# SAM70.net
KiCad netlist of a schematic drawn in Altium Designer
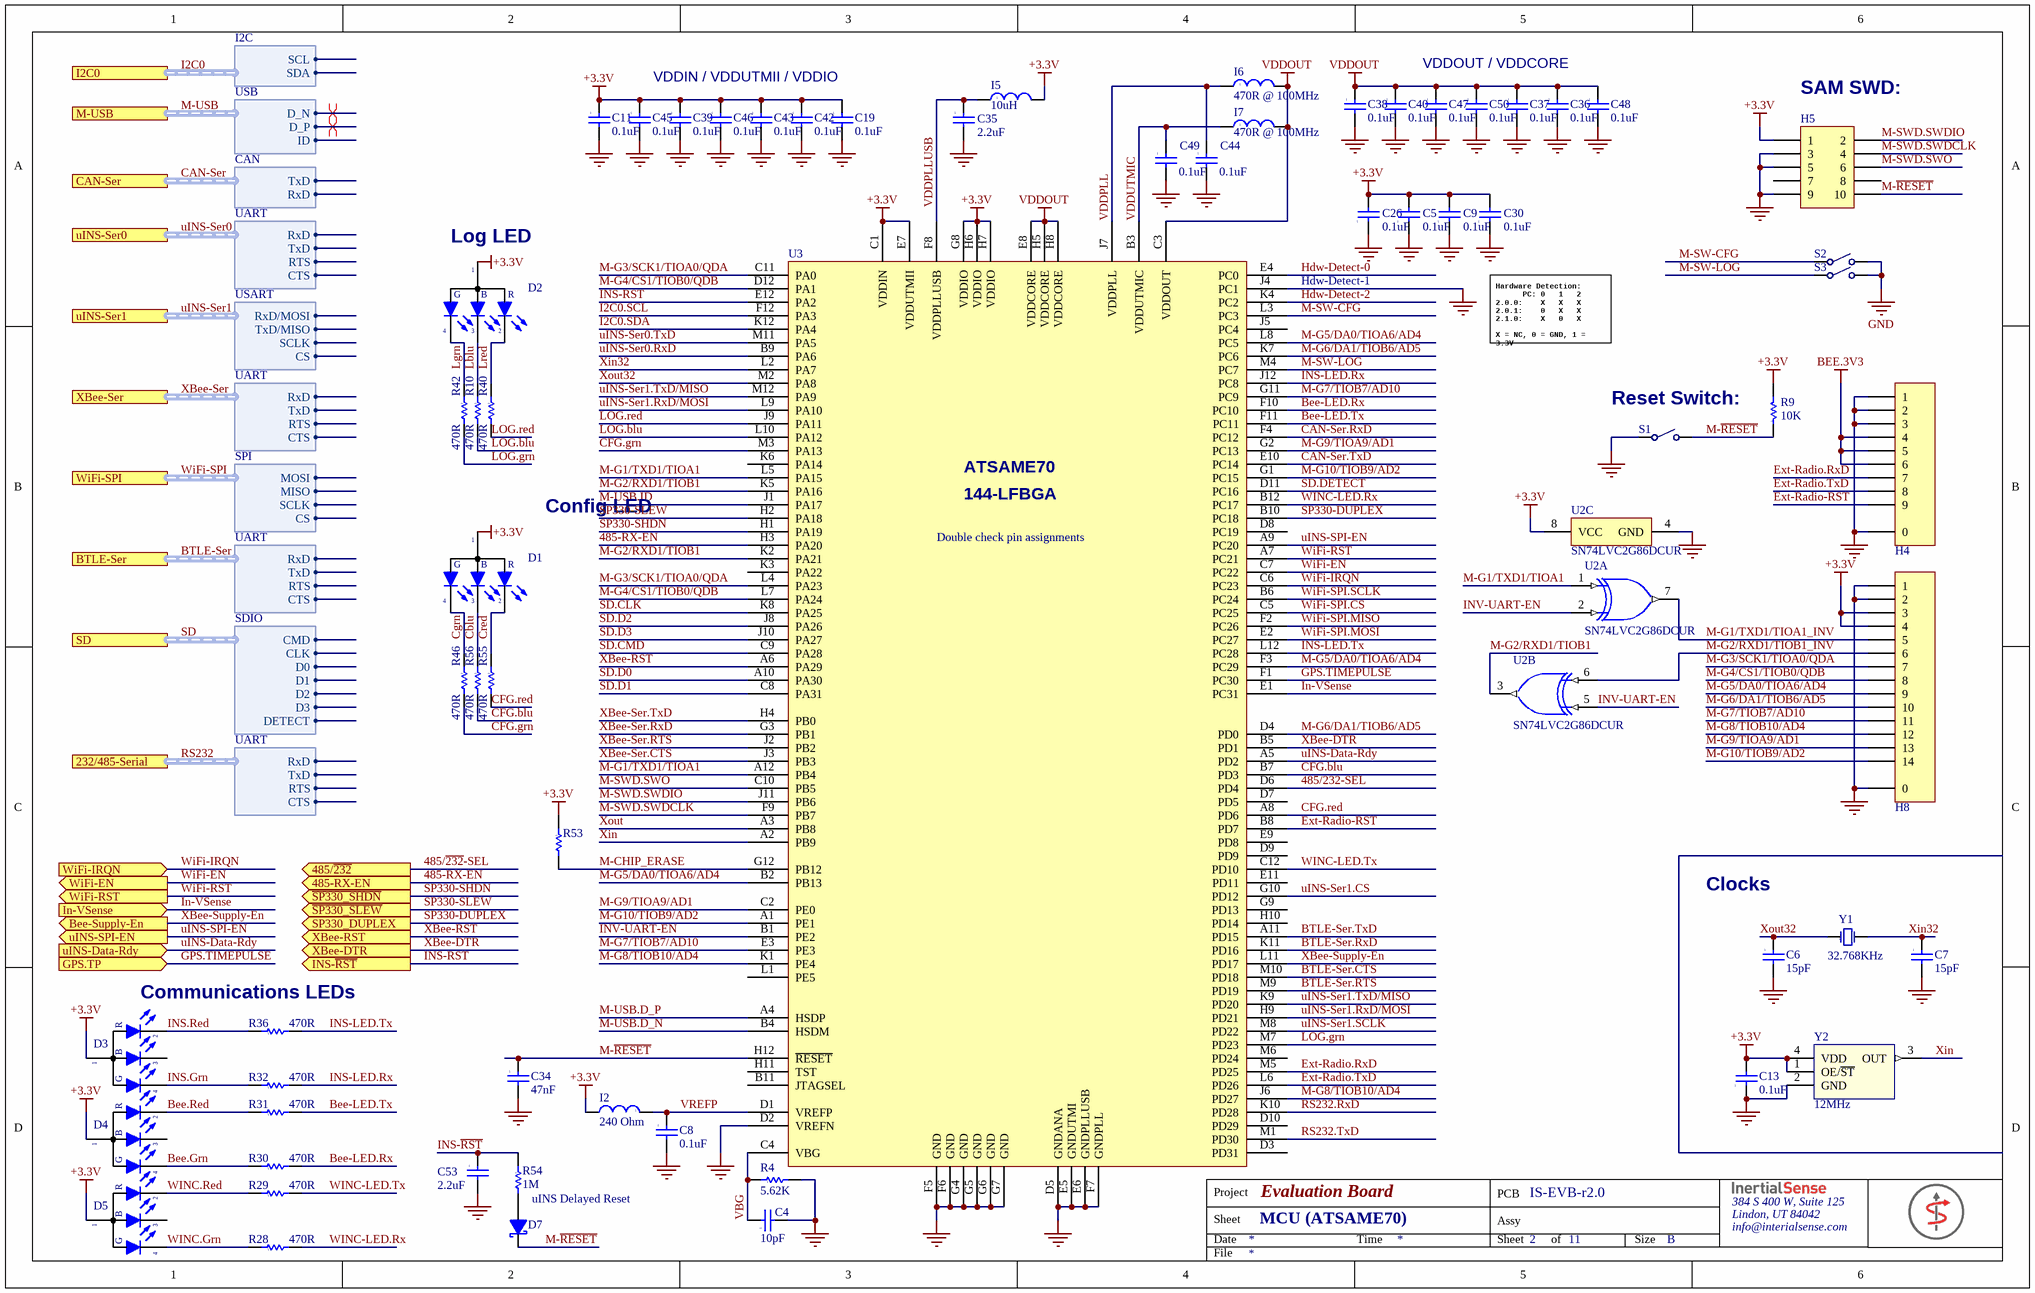
[diagram p0: SAM70.SchDoc]

(export (version "E")
  (design (tool "Eeschema 10.0.6"))
  (components
    (comp (ref "C4")
      (value "10pF")
      (footprint "0402")
      (description "CAP CER 10PF 50V C0G 0402")
      (fields
        (field (name "MANUFACTURER") "TDK")
        (field (name "MANUFACTURER PART NUMBER") "C1005C0G1H100D050BA")
        (field (name "PUBLISHER") "Altium Limited")
      )
      (libsource (lib "General") (part "Cap"))
    )
    (comp (ref "C5")
      (value "0.1uF")
      (footprint "0402")
      (description "CAP CER .10UF 50V X7R 10% 0402")
      (fields
        (field (name "MANUFACTURER") "TDK Corporation")
        (field (name "MANUFACTURER PART NUMBER") "C1005X7R1H104K")
        (field (name "PUBLISHER") "Altium Limited")
      )
      (libsource (lib "") (part "Cap_1"))
    )
    (comp (ref "C6")
      (value "15pF")
      (footprint "0402")
      (description "CAP CER 15PF 16V C0G/NP0 0402")
      (fields
        (field (name "MANUFACTURER") "KEMET")
        (field (name "MANUFACTURER PART NUMBER") "C0402C150J4GACTU")
        (field (name "PUBLISHER") "Altium Limited")
      )
      (libsource (lib "General") (part "Cap"))
    )
    (comp (ref "C7")
      (value "15pF")
      (footprint "0402")
      (description "CAP CER 15PF 16V C0G/NP0 0402")
      (fields
        (field (name "MANUFACTURER") "KEMET")
        (field (name "MANUFACTURER PART NUMBER") "C0402C150J4GACTU")
        (field (name "PUBLISHER") "Altium Limited")
      )
      (libsource (lib "General") (part "Cap"))
    )
    (comp (ref "C8")
      (value "0.1uF")
      (footprint "0201")
      (description "CAP CER 0.1UF 25V X5R 0201")
      (fields
        (field (name "MANUFACTURER") "Murata")
        (field (name "MANUFACTURER PART NUMBER") "GRM033R6YA104KE14D")
        (field (name "PUBLISHER") "Altium Limited")
      )
      (libsource (lib "General") (part "Cap"))
    )
    (comp (ref "C9")
      (value "0.1uF")
      (footprint "0402")
      (description "CAP CER .10UF 50V X7R 10% 0402")
      (fields
        (field (name "MANUFACTURER") "TDK Corporation")
        (field (name "MANUFACTURER PART NUMBER") "C1005X7R1H104K")
        (field (name "PUBLISHER") "Altium Limited")
      )
      (libsource (lib "") (part "Cap_1"))
    )
    (comp (ref "C11")
      (value "0.1uF")
      (footprint "0201")
      (description "CAP CER 0.1UF 25V X5R 0201")
      (fields
        (field (name "MANUFACTURER") "Murata")
        (field (name "MANUFACTURER PART NUMBER") "GRM033R6YA104KE14D")
        (field (name "PUBLISHER") "Altium Limited")
      )
      (libsource (lib "General") (part "Cap"))
    )
    (comp (ref "C13")
      (value "0.1uF")
      (footprint "0402")
      (description "CAP CER .10UF 50V X7R 10% 0402")
      (fields
        (field (name "MANUFACTURER") "TDK Corporation")
        (field (name "MANUFACTURER PART NUMBER") "C1005X7R1H104K")
        (field (name "PUBLISHER") "Altium Limited")
      )
      (libsource (lib "") (part "Cap_1"))
    )
    (comp (ref "C19")
      (value "0.1uF")
      (footprint "0201")
      (description "CAP CER 0.1UF 25V X5R 0201")
      (fields
        (field (name "MANUFACTURER") "Murata")
        (field (name "MANUFACTURER PART NUMBER") "GRM033R6YA104KE14D")
        (field (name "PUBLISHER") "Altium Limited")
      )
      (libsource (lib "General") (part "Cap"))
    )
    (comp (ref "C26")
      (value "0.1uF")
      (footprint "0402")
      (description "CAP CER .10UF 50V X7R 10% 0402")
      (fields
        (field (name "MANUFACTURER") "TDK Corporation")
        (field (name "MANUFACTURER PART NUMBER") "C1005X7R1H104K")
        (field (name "PUBLISHER") "Altium Limited")
      )
      (libsource (lib "") (part "Cap_1"))
    )
    (comp (ref "C30")
      (value "0.1uF")
      (footprint "0402")
      (description "CAP CER .10UF 50V X7R 10% 0402")
      (fields
        (field (name "MANUFACTURER") "TDK Corporation")
        (field (name "MANUFACTURER PART NUMBER") "C1005X7R1H104K")
        (field (name "PUBLISHER") "Altium Limited")
      )
      (libsource (lib "") (part "Cap_1"))
    )
    (comp (ref "C34")
      (value "47nF")
      (footprint "0402")
      (description "CAP CER 0.047UF 16V Y5V 0402")
      (fields
        (field (name "MANUFACTURER") "Yageo")
        (field (name "MANUFACTURER PART NUMBER") "CC0402ZRY5V7BB473")
        (field (name "PUBLISHER") "Altium Limited")
      )
      (libsource (lib "General") (part "Cap"))
    )
    (comp (ref "C35")
      (value "Cap")
      (footprint "0603")
      (description "CAP CER 2.2UF 6.3V X5R 0603")
      (fields
        (field (name "MANUFACTURER") "Samsung")
        (field (name "MANUFACTURER PART NUMBER") "CL10A225KQ8NNWC")
        (field (name "CAPACITANCE") "2.2uF")
      )
      (libsource (lib "General") (part "Cap"))
    )
    (comp (ref "C36")
      (value "0.1uF")
      (footprint "0201")
      (description "CAP CER 0.1UF 25V X5R 0201")
      (fields
        (field (name "MANUFACTURER") "Murata")
        (field (name "MANUFACTURER PART NUMBER") "GRM033R6YA104KE14D")
        (field (name "PUBLISHER") "Altium Limited")
      )
      (libsource (lib "General") (part "Cap"))
    )
    (comp (ref "C37")
      (value "0.1uF")
      (footprint "0201")
      (description "CAP CER 0.1UF 25V X5R 0201")
      (fields
        (field (name "MANUFACTURER") "Murata")
        (field (name "MANUFACTURER PART NUMBER") "GRM033R6YA104KE14D")
        (field (name "PUBLISHER") "Altium Limited")
      )
      (libsource (lib "General") (part "Cap"))
    )
    (comp (ref "C38")
      (value "0.1uF")
      (footprint "0201")
      (description "CAP CER 0.1UF 25V X5R 0201")
      (fields
        (field (name "MANUFACTURER") "Murata")
        (field (name "MANUFACTURER PART NUMBER") "GRM033R6YA104KE14D")
        (field (name "PUBLISHER") "Altium Limited")
      )
      (libsource (lib "General") (part "Cap"))
    )
    (comp (ref "C39")
      (value "0.1uF")
      (footprint "0201")
      (description "CAP CER 0.1UF 25V X5R 0201")
      (fields
        (field (name "MANUFACTURER") "Murata")
        (field (name "MANUFACTURER PART NUMBER") "GRM033R6YA104KE14D")
        (field (name "PUBLISHER") "Altium Limited")
      )
      (libsource (lib "General") (part "Cap"))
    )
    (comp (ref "C40")
      (value "0.1uF")
      (footprint "0201")
      (description "CAP CER 0.1UF 25V X5R 0201")
      (fields
        (field (name "MANUFACTURER") "Murata")
        (field (name "MANUFACTURER PART NUMBER") "GRM033R6YA104KE14D")
        (field (name "PUBLISHER") "Altium Limited")
      )
      (libsource (lib "General") (part "Cap"))
    )
    (comp (ref "C42")
      (value "0.1uF")
      (footprint "0201")
      (description "CAP CER 0.1UF 25V X5R 0201")
      (fields
        (field (name "MANUFACTURER") "Murata")
        (field (name "MANUFACTURER PART NUMBER") "GRM033R6YA104KE14D")
        (field (name "PUBLISHER") "Altium Limited")
      )
      (libsource (lib "General") (part "Cap"))
    )
    (comp (ref "C43")
      (value "0.1uF")
      (footprint "0201")
      (description "CAP CER 0.1UF 25V X5R 0201")
      (fields
        (field (name "MANUFACTURER") "Murata")
        (field (name "MANUFACTURER PART NUMBER") "GRM033R6YA104KE14D")
        (field (name "PUBLISHER") "Altium Limited")
      )
      (libsource (lib "General") (part "Cap"))
    )
    (comp (ref "C44")
      (value "0.1uF")
      (footprint "0201")
      (description "CAP CER 0.1UF 25V X5R 0201")
      (fields
        (field (name "MANUFACTURER") "Murata")
        (field (name "MANUFACTURER PART NUMBER") "GRM033R6YA104KE14D")
        (field (name "PUBLISHER") "Altium Limited")
      )
      (libsource (lib "General") (part "Cap"))
    )
    (comp (ref "C45")
      (value "0.1uF")
      (footprint "0201")
      (description "CAP CER 0.1UF 25V X5R 0201")
      (fields
        (field (name "MANUFACTURER") "Murata")
        (field (name "MANUFACTURER PART NUMBER") "GRM033R6YA104KE14D")
        (field (name "PUBLISHER") "Altium Limited")
      )
      (libsource (lib "General") (part "Cap"))
    )
    (comp (ref "C46")
      (value "0.1uF")
      (footprint "0201")
      (description "CAP CER 0.1UF 25V X5R 0201")
      (fields
        (field (name "MANUFACTURER") "Murata")
        (field (name "MANUFACTURER PART NUMBER") "GRM033R6YA104KE14D")
        (field (name "PUBLISHER") "Altium Limited")
      )
      (libsource (lib "General") (part "Cap"))
    )
    (comp (ref "C47")
      (value "0.1uF")
      (footprint "0201")
      (description "CAP CER 0.1UF 25V X5R 0201")
      (fields
        (field (name "MANUFACTURER") "Murata")
        (field (name "MANUFACTURER PART NUMBER") "GRM033R6YA104KE14D")
        (field (name "PUBLISHER") "Altium Limited")
      )
      (libsource (lib "General") (part "Cap"))
    )
    (comp (ref "C48")
      (value "0.1uF")
      (footprint "0201")
      (description "CAP CER 0.1UF 25V X5R 0201")
      (fields
        (field (name "MANUFACTURER") "Murata")
        (field (name "MANUFACTURER PART NUMBER") "GRM033R6YA104KE14D")
        (field (name "PUBLISHER") "Altium Limited")
      )
      (libsource (lib "General") (part "Cap"))
    )
    (comp (ref "C49")
      (value "0.1uF")
      (footprint "0201")
      (description "CAP CER 0.1UF 25V X5R 0201")
      (fields
        (field (name "MANUFACTURER") "Murata")
        (field (name "MANUFACTURER PART NUMBER") "GRM033R6YA104KE14D")
        (field (name "PUBLISHER") "Altium Limited")
      )
      (libsource (lib "General") (part "Cap"))
    )
    (comp (ref "C50")
      (value "0.1uF")
      (footprint "0201")
      (description "CAP CER 0.1UF 25V X5R 0201")
      (fields
        (field (name "MANUFACTURER") "Murata")
        (field (name "MANUFACTURER PART NUMBER") "GRM033R6YA104KE14D")
        (field (name "PUBLISHER") "Altium Limited")
      )
      (libsource (lib "General") (part "Cap"))
    )
    (comp (ref "C53")
      (value "Cap")
      (footprint "0603")
      (description "CAP CER 2.2UF 6.3V X5R 0603")
      (fields
        (field (name "MANUFACTURER") "Samsung")
        (field (name "MANUFACTURER PART NUMBER") "CL10A225KQ8NNWC")
        (field (name "CAPACITANCE") "2.2uF")
      )
      (libsource (lib "General") (part "Cap"))
    )
    (comp (ref "D1")
      (value "LED-RGB")
      (footprint "LED0404")
      (description "LED RGB DIFFUSED 0404 SMD")
      (fields
        (field (name "MANUFACTURER") "Rohm Semiconductor")
        (field (name "MANUFACTURER PART NUMBER") "SMLP34RGB2W3")
        (field (name "PUBLISHER") "Altium Limited")
      )
      (libsource (lib "General") (part "LED-RGB"))
    )
    (comp (ref "D2")
      (value "LED-RGB")
      (footprint "LED0404")
      (description "LED RGB DIFFUSED 0404 SMD")
      (fields
        (field (name "MANUFACTURER") "Rohm Semiconductor")
        (field (name "MANUFACTURER PART NUMBER") "SMLP34RGB2W3")
        (field (name "PUBLISHER") "Altium Limited")
      )
      (libsource (lib "General") (part "LED-RGB"))
    )
    (comp (ref "D3")
      (value "LED-RGB")
      (footprint "LED0404")
      (description "LED RGB DIFFUSED 0404 SMD")
      (fields
        (field (name "MANUFACTURER") "Rohm Semiconductor")
        (field (name "MANUFACTURER PART NUMBER") "SMLP34RGB2W3")
        (field (name "PUBLISHER") "Altium Limited")
      )
      (libsource (lib "General") (part "LED-RGB"))
    )
    (comp (ref "D4")
      (value "LED-RGB")
      (footprint "LED0404")
      (description "LED RGB DIFFUSED 0404 SMD")
      (fields
        (field (name "MANUFACTURER") "Rohm Semiconductor")
        (field (name "MANUFACTURER PART NUMBER") "SMLP34RGB2W3")
        (field (name "PUBLISHER") "Altium Limited")
      )
      (libsource (lib "General") (part "LED-RGB"))
    )
    (comp (ref "D5")
      (value "LED-RGB")
      (footprint "LED0404")
      (description "LED RGB DIFFUSED 0404 SMD")
      (fields
        (field (name "MANUFACTURER") "Rohm Semiconductor")
        (field (name "MANUFACTURER PART NUMBER") "SMLP34RGB2W3")
        (field (name "PUBLISHER") "Altium Limited")
      )
      (libsource (lib "General") (part "LED-RGB"))
    )
    (comp (ref "D7")
      (value "Diode - Schottky")
      (footprint "D0603B")
      (description "DIODE SCHOTTKY 30V 2A 0603")
      (fields
        (field (name "MANUFACTURER") "Vishay")
        (field (name "MANUFACTURER PART NUMBER") "VSKY20301608-G4-08")
      )
      (libsource (lib "General") (part "Diode - Schottky"))
    )
    (comp (ref "H4")
      (value "Hdr - 9pin - mount")
      (footprint "SM09B-GHS-TB(LF)(SN)")
      (description "CONN HEADER GH SIDE 9POS 1.25MM")
      (fields
        (field (name "MANUFACTURER") "JST")
        (field (name "MANUFACTURER PART NUMBER") "SM09B-GHS-TB(LF)(SN)")
      )
      (libsource (lib "Connectors") (part "Hdr - 9pin - mount"))
    )
    (comp (ref "H5")
      (value "Hdr - 5x2pin")
      (footprint "FTSH-105-01-L-DV-K-A-P")
      (description "CONN HEADER 10POS DUAL .05\" SMD")
      (fields
        (field (name "MANUFACTURER") "Samtec")
        (field (name "MANUFACTURER PART NUMBER") "FTSH-105-01-L-DV-K-A-P")
      )
      (libsource (lib "Connectors") (part "Hdr - 5x2pin"))
    )
    (comp (ref "H8")
      (value "Hdr - 14pin - mount")
      (footprint "SM14B-GHS-TB(LF)(SN)")
      (description "CONN HEADER GH SIDE 14POS 1.25MM")
      (fields
        (field (name "MANUFACTURER") "JST")
        (field (name "MANUFACTURER PART NUMBER") "SM14B-GHS-TB(LF)(SN)")
      )
      (libsource (lib "Connectors") (part "Hdr - 14pin - mount"))
    )
    (comp (ref "I2")
      (value "240 Ohm")
      (footprint "0201")
      (description "FERRITE BEAD 240 OHM 0201 1LN")
      (fields
        (field (name "MANUFACTURER") "TDK Corporation")
        (field (name "MANUFACTURER PART NUMBER") "MMZ0603S241HT000")
      )
      (libsource (lib "General") (part "Inductor"))
    )
    (comp (ref "I5")
      (value "Inductor")
      (footprint "0806")
      (description "FIXED IND 10UH 350MA 1.066 OHM")
      (fields
        (field (name "MANUFACTURER") "Taiyo Yuden")
        (field (name "MANUFACTURER PART NUMBER") "CBC2016T100M")
        (field (name "INDUCTANCE") "10uH")
      )
      (libsource (lib "") (part "Inductor_1"))
    )
    (comp (ref "I6")
      (value "470R @ 100MHz")
      (footprint "0402")
      (description "FERRITE BEAD 470 OHM 0402")
      (fields
        (field (name "MANUFACTURER") "Taiyo Yuden")
        (field (name "MANUFACTURER PART NUMBER") "BK1005HM471-T")
      )
      (libsource (lib "") (part "Inductor_1"))
    )
    (comp (ref "I7")
      (value "470R @ 100MHz")
      (footprint "0402")
      (description "FERRITE BEAD 470 OHM 0402")
      (fields
        (field (name "MANUFACTURER") "Taiyo Yuden")
        (field (name "MANUFACTURER PART NUMBER") "BK1005HM471-T")
      )
      (libsource (lib "") (part "Inductor_1"))
    )
    (comp (ref "R4")
      (value "5.62K")
      (footprint "R0402")
      (description "RES SMD 5.62K OHM 1% 1/10W 0402")
      (fields
        (field (name "MANUFACTURER") "Panasonic")
        (field (name "MANUFACTURER PART NUMBER") "ERJ-2RKF5621X")
      )
      (libsource (lib "General") (part "Res"))
    )
    (comp (ref "R9")
      (value "10K")
      (footprint "R0402")
      (description "RES 10K OHM 1/16W 1% 0402 SMD")
      (fields
        (field (name "MANUFACTURER") "Panasonic")
        (field (name "MANUFACTURER PART NUMBER") "ERJ-2RKF1002X")
      )
      (libsource (lib "") (part "Res_1"))
    )
    (comp (ref "R10")
      (value "470R")
      (footprint "R0402")
      (description "RES SMD 470 OHM 5% 1/16W 0402")
      (fields
        (field (name "MANUFACTURER") "Vishay Dale")
        (field (name "MANUFACTURER PART NUMBER") "CRCW0402470RJNED")
      )
      (libsource (lib "General") (part "Res"))
    )
    (comp (ref "R28")
      (value "470R")
      (footprint "R0402")
      (description "RES SMD 470 OHM 5% 1/16W 0402")
      (fields
        (field (name "MANUFACTURER") "Vishay Dale")
        (field (name "MANUFACTURER PART NUMBER") "CRCW0402470RJNED")
      )
      (libsource (lib "General") (part "Res"))
    )
    (comp (ref "R29")
      (value "470R")
      (footprint "R0402")
      (description "RES SMD 470 OHM 5% 1/16W 0402")
      (fields
        (field (name "MANUFACTURER") "Vishay Dale")
        (field (name "MANUFACTURER PART NUMBER") "CRCW0402470RJNED")
      )
      (libsource (lib "General") (part "Res"))
    )
    (comp (ref "R30")
      (value "470R")
      (footprint "R0402")
      (description "RES SMD 470 OHM 5% 1/16W 0402")
      (fields
        (field (name "MANUFACTURER") "Vishay Dale")
        (field (name "MANUFACTURER PART NUMBER") "CRCW0402470RJNED")
      )
      (libsource (lib "General") (part "Res"))
    )
    (comp (ref "R31")
      (value "470R")
      (footprint "R0402")
      (description "RES SMD 470 OHM 5% 1/16W 0402")
      (fields
        (field (name "MANUFACTURER") "Vishay Dale")
        (field (name "MANUFACTURER PART NUMBER") "CRCW0402470RJNED")
      )
      (libsource (lib "General") (part "Res"))
    )
    (comp (ref "R32")
      (value "470R")
      (footprint "R0402")
      (description "RES SMD 470 OHM 5% 1/16W 0402")
      (fields
        (field (name "MANUFACTURER") "Vishay Dale")
        (field (name "MANUFACTURER PART NUMBER") "CRCW0402470RJNED")
      )
      (libsource (lib "General") (part "Res"))
    )
    (comp (ref "R36")
      (value "470R")
      (footprint "R0402")
      (description "RES SMD 470 OHM 5% 1/16W 0402")
      (fields
        (field (name "MANUFACTURER") "Vishay Dale")
        (field (name "MANUFACTURER PART NUMBER") "CRCW0402470RJNED")
      )
      (libsource (lib "General") (part "Res"))
    )
    (comp (ref "R40")
      (value "470R")
      (footprint "R0402")
      (description "RES SMD 470 OHM 5% 1/16W 0402")
      (fields
        (field (name "MANUFACTURER") "Vishay Dale")
        (field (name "MANUFACTURER PART NUMBER") "CRCW0402470RJNED")
      )
      (libsource (lib "General") (part "Res"))
    )
    (comp (ref "R42")
      (value "470R")
      (footprint "R0402")
      (description "RES SMD 470 OHM 5% 1/16W 0402")
      (fields
        (field (name "MANUFACTURER") "Vishay Dale")
        (field (name "MANUFACTURER PART NUMBER") "CRCW0402470RJNED")
      )
      (libsource (lib "General") (part "Res"))
    )
    (comp (ref "R46")
      (value "470R")
      (footprint "R0402")
      (description "RES SMD 470 OHM 5% 1/16W 0402")
      (fields
        (field (name "MANUFACTURER") "Vishay Dale")
        (field (name "MANUFACTURER PART NUMBER") "CRCW0402470RJNED")
      )
      (libsource (lib "General") (part "Res"))
    )
    (comp (ref "R53")
      (value "Res")
      (footprint "R0402")
      (description "RES SMD 0402 NO LOAD")
      (libsource (lib "General") (part "Res"))
    )
    (comp (ref "R54")
      (value "1M")
      (footprint "R0402")
      (description "RES SMD 1M OHM 1% 1/16W 0402")
      (fields (field (name "TOLERANCE") "1%") (field (name "Comment") "Res"))
      (libsource (lib "General") (part "Res"))
    )
    (comp (ref "R55")
      (value "470R")
      (footprint "R0402")
      (description "RES SMD 470 OHM 5% 1/16W 0402")
      (fields
        (field (name "MANUFACTURER") "Vishay Dale")
        (field (name "MANUFACTURER PART NUMBER") "CRCW0402470RJNED")
      )
      (libsource (lib "General") (part "Res"))
    )
    (comp (ref "R56")
      (value "470R")
      (footprint "R0402")
      (description "RES SMD 470 OHM 5% 1/16W 0402")
      (fields
        (field (name "MANUFACTURER") "Vishay Dale")
        (field (name "MANUFACTURER PART NUMBER") "CRCW0402470RJNED")
      )
      (libsource (lib "General") (part "Res"))
    )
    (comp (ref "S1")
      (value "SPST Switch")
      (footprint "PTS810")
      (description "SWITCH TACTILE SPST-NO 0.05A 16V")
      (fields
        (field (name "MANUFACTURER") "ITT C&K")
        (field (name "MANUFACTURER PART NUMBER") "PTS810SJK250SMTRLFS")
      )
      (libsource (lib "General") (part "Switch SPST"))
    )
    (comp (ref "S2")
      (value "SPST Switch")
      (footprint "PTS810")
      (description "SWITCH TACTILE SPST-NO 0.05A 16V")
      (fields
        (field (name "MANUFACTURER") "ITT C&K")
        (field (name "MANUFACTURER PART NUMBER") "PTS810SJK250SMTRLFS")
      )
      (libsource (lib "General") (part "Switch SPST"))
    )
    (comp (ref "S3")
      (value "SPST Switch")
      (footprint "PTS810")
      (description "SWITCH TACTILE SPST-NO 0.05A 16V")
      (fields
        (field (name "MANUFACTURER") "ITT C&K")
        (field (name "MANUFACTURER PART NUMBER") "PTS810SJK250SMTRLFS")
      )
      (libsource (lib "General") (part "Switch SPST"))
    )
    (comp (ref "U2")
      (value "SN74LVC2G86DCUR")
      (footprint "DCU0008A_N")
      (description "IC GATE XOR 2CH 2-INP US8")
      (fields
        (field (name "GENERIC PART NUMBER") "SN74LVC2G86")
        (field (name "MANUFACTURER") "Texas Instruments")
      )
      (libsource (lib "TI_Logic_Little_Logic") (part "SN74LVC2G86DCUR"))
    )
    (comp (ref "U3")
      (value "ATSAME70-144")
      (footprint "BGA144C80P12X12_1000X1000X140")
      (description "IC MCU 32BIT 1MB FLASH 144LFBGA")
      (fields
        (field (name "MANUFACTURER") "Microchip")
        (field (name "MANUFACTURER PART NUMBER") "ATSAME70Q20B-CNT")
      )
      (libsource (lib "ICs") (part "ATSAME70-144"))
    )
    (comp (ref "Y1")
      (value "32.768KHz")
      (footprint "CRYMP2012X06L")
      (description "CRYSTAL 32.7680KHZ 9PF SMD")
      (fields
        (field (name "MANUFACTURER") "Abracon LLC")
        (field (name "MANUFACTURER PART NUMBER") "ABS06-32.768KHZ-9-1-T")
      )
      (libsource (lib "General") (part "Crystal"))
    )
    (comp (ref "Y2")
      (value "12MHz")
      (footprint "ABM10_2.5_x_2.0")
      (description "OSC XO 12.000MHZ HCMOS SMD")
      (fields
        (field (name "MANUFACTURER") "ECS Inc.")
        (field (name "MANUFACTURER PART NUMBER") "ECS-2520S33-120-FN-TR")
      )
      (libsource (lib "General") (part "Oscillator2"))
    )
  )
  (nets
    (net (code "11") (name "+3.3V") (class "Default")
      (node (ref "C11") (pin "1") (pinfunction "1_1") (pintype "passive"))
      (node (ref "C13") (pin "2") (pinfunction "2_2") (pintype "passive"))
      (node (ref "C19") (pin "1") (pinfunction "1_1") (pintype "passive"))
      (node (ref "C26") (pin "2") (pinfunction "2_2") (pintype "passive"))
      (node (ref "C30") (pin "2") (pinfunction "2_2") (pintype "passive"))
      (node (ref "C39") (pin "1") (pinfunction "1_1") (pintype "passive"))
      (node (ref "C42") (pin "1") (pinfunction "1_1") (pintype "passive"))
      (node (ref "C43") (pin "1") (pinfunction "1_1") (pintype "passive"))
      (node (ref "C45") (pin "1") (pinfunction "1_1") (pintype "passive"))
      (node (ref "C46") (pin "1") (pinfunction "1_1") (pintype "passive"))
      (node (ref "C5") (pin "2") (pinfunction "2_2") (pintype "passive"))
      (node (ref "C9") (pin "2") (pinfunction "2_2") (pintype "passive"))
      (node (ref "D1") (pin "1") (pinfunction "1_1") (pintype "passive"))
      (node (ref "D2") (pin "1") (pinfunction "1_1") (pintype "passive"))
      (node (ref "D3") (pin "1") (pinfunction "1_1") (pintype "passive"))
      (node (ref "D4") (pin "1") (pinfunction "1_1") (pintype "passive"))
      (node (ref "D5") (pin "1") (pinfunction "1_1") (pintype "passive"))
      (node (ref "H5") (pin "1") (pinfunction "1_1") (pintype "passive"))
      (node (ref "H8") (pin "3") (pinfunction "3_3") (pintype "passive"))
      (node (ref "H8") (pin "4") (pinfunction "4_4") (pintype "passive"))
      (node (ref "I2") (pin "2") (pinfunction "2_2") (pintype "passive"))
      (node (ref "I5") (pin "2") (pinfunction "2_2") (pintype "passive"))
      (node (ref "R53") (pin "1") (pinfunction "1_1") (pintype "passive"))
      (node (ref "R9") (pin "2") (pinfunction "2_2") (pintype "passive"))
      (node (ref "U2") (pin "8") (pinfunction "VCC_8") (pintype "power_in"))
      (node (ref "U3") (pin "C1") (pinfunction "VDDIN_C1") (pintype "passive"))
      (node (ref "U3") (pin "E7") (pinfunction "VDDUTMII_E7") (pintype "passive"))
      (node (ref "U3") (pin "G8") (pinfunction "VDDIO_G8") (pintype "passive"))
      (node (ref "U3") (pin "H6") (pinfunction "VDDIO_H6") (pintype "passive"))
      (node (ref "U3") (pin "H7") (pinfunction "VDDIO_H7") (pintype "passive"))
      (node (ref "Y2") (pin "1") (pinfunction "OE/~{ST}_1") (pintype "passive"))
      (node (ref "Y2") (pin "4") (pinfunction "VDD_4") (pintype "passive"))
    )
    (net (code "12") (name "/485-RX-EN") (class "Default")
      (node (ref "U3") (pin "H3") (pinfunction "PA20_H3") (pintype "passive"))
    )
    (net (code "13") (name "/485{slash}~{232}-SEL") (class "Default")
      (node (ref "U3") (pin "D6") (pinfunction "PD4_D6") (pintype "passive"))
    )
    (net (code "14") (name "/BTLE-Ser.CTS") (class "Default")
      (node (ref "U3") (pin "M10") (pinfunction "PD18_M10") (pintype "passive"))
    )
    (net (code "15") (name "/BTLE-Ser.RTS") (class "Default")
      (node (ref "U3") (pin "M9") (pinfunction "PD19_M9") (pintype "passive"))
    )
    (net (code "16") (name "/BTLE-Ser.RxD") (class "Default")
      (node (ref "U3") (pin "K11") (pinfunction "PD16_K11") (pintype "passive"))
    )
    (net (code "17") (name "/BTLE-Ser.TxD") (class "Default")
      (node (ref "U3") (pin "A11") (pinfunction "PD15_A11") (pintype "passive"))
    )
    (net (code "19") (name "/Bee-LED.Rx") (class "Default")
      (node (ref "R30") (pin "2") (pinfunction "2_2") (pintype "passive"))
      (node (ref "U3") (pin "F10") (pinfunction "PC10_F10") (pintype "passive"))
    )
    (net (code "20") (name "/Bee-LED.Tx") (class "Default")
      (node (ref "R31") (pin "2") (pinfunction "2_2") (pintype "passive"))
      (node (ref "U3") (pin "F11") (pinfunction "PC11_F11") (pintype "passive"))
    )
    (net (code "21") (name "/Bee.Grn") (class "Default")
      (node (ref "D4") (pin "4") (pinfunction "4_4") (pintype "passive"))
      (node (ref "R30") (pin "1") (pinfunction "1_1") (pintype "passive"))
    )
    (net (code "22") (name "/Bee.Red") (class "Default")
      (node (ref "D4") (pin "2") (pinfunction "2_2") (pintype "passive"))
      (node (ref "R31") (pin "1") (pinfunction "1_1") (pintype "passive"))
    )
    (net (code "23") (name "/CAN-Ser.RxD") (class "Default")
      (node (ref "U3") (pin "F4") (pinfunction "PC12_F4") (pintype "passive"))
    )
    (net (code "24") (name "/CAN-Ser.TxD") (class "Default")
      (node (ref "U3") (pin "E10") (pinfunction "PC14_E10") (pintype "passive"))
    )
    (net (code "26") (name "/CFG.blu") (class "Default")
      (node (ref "R56") (pin "2") (pinfunction "2_2") (pintype "passive"))
      (node (ref "U3") (pin "B7") (pinfunction "PD3_B7") (pintype "passive"))
    )
    (net (code "27") (name "/CFG.grn") (class "Default")
      (node (ref "R46") (pin "2") (pinfunction "2_2") (pintype "passive"))
      (node (ref "U3") (pin "M3") (pinfunction "PA13_M3") (pintype "passive"))
    )
    (net (code "28") (name "/CFG.red") (class "Default")
      (node (ref "R55") (pin "2") (pinfunction "2_2") (pintype "passive"))
      (node (ref "U3") (pin "A8") (pinfunction "PD6_A8") (pintype "passive"))
    )
    (net (code "29") (name "/Cblu") (class "Default")
      (node (ref "D1") (pin "3") (pinfunction "3_3") (pintype "passive"))
      (node (ref "R56") (pin "1") (pinfunction "1_1") (pintype "passive"))
    )
    (net (code "30") (name "/Cgrn") (class "Default")
      (node (ref "D1") (pin "4") (pinfunction "4_4") (pintype "passive"))
      (node (ref "R46") (pin "1") (pinfunction "1_1") (pintype "passive"))
    )
    (net (code "31") (name "/Cred") (class "Default")
      (node (ref "D1") (pin "2") (pinfunction "2_2") (pintype "passive"))
      (node (ref "R55") (pin "1") (pinfunction "1_1") (pintype "passive"))
    )
    (net (code "32") (name "/Ext-Radio-RST") (class "Default")
      (node (ref "H4") (pin "9") (pinfunction "9_9") (pintype "passive"))
      (node (ref "U3") (pin "B8") (pinfunction "PD7_B8") (pintype "passive"))
    )
    (net (code "33") (name "/Ext-Radio.RxD") (class "Default")
      (node (ref "H4") (pin "7") (pinfunction "7_7") (pintype "passive"))
      (node (ref "U3") (pin "M5") (pinfunction "PD25_M5") (pintype "passive"))
    )
    (net (code "34") (name "/Ext-Radio.TxD") (class "Default")
      (node (ref "H4") (pin "8") (pinfunction "8_8") (pintype "passive"))
      (node (ref "U3") (pin "L6") (pinfunction "PD26_L6") (pintype "passive"))
    )
    (net (code "35") (name "/GPS.TIMEPULSE") (class "Default")
      (node (ref "U3") (pin "F1") (pinfunction "PC30_F1") (pintype "passive"))
    )
    (net (code "36") (name "/Hdw-Detect-0") (class "Default")
      (node (ref "U3") (pin "E4") (pinfunction "PC0_E4") (pintype "passive"))
    )
    (net (code "37") (name "/Hdw-Detect-2") (class "Default")
      (node (ref "U3") (pin "K4") (pinfunction "PC2_K4") (pintype "passive"))
    )
    (net (code "38") (name "/I2C0.SCL") (class "Default")
      (node (ref "U3") (pin "F12") (pinfunction "PA3_F12") (pintype "passive"))
    )
    (net (code "39") (name "/I2C0.SDA") (class "Default")
      (node (ref "U3") (pin "K12") (pinfunction "PA4_K12") (pintype "passive"))
    )
    (net (code "41") (name "/INS-LED.Rx") (class "Default")
      (node (ref "R32") (pin "2") (pinfunction "2_2") (pintype "passive"))
      (node (ref "U3") (pin "J12") (pinfunction "PC8_J12") (pintype "passive"))
    )
    (net (code "42") (name "/INS-LED.Tx") (class "Default")
      (node (ref "R36") (pin "2") (pinfunction "2_2") (pintype "passive"))
      (node (ref "U3") (pin "L12") (pinfunction "PC28_L12") (pintype "passive"))
    )
    (net (code "43") (name "/INS-~{RST}") (class "Default")
      (node (ref "C53") (pin "1") (pinfunction "1_1") (pintype "passive"))
      (node (ref "R54") (pin "1") (pinfunction "1_1") (pintype "passive"))
      (node (ref "U3") (pin "E12") (pinfunction "PA2_E12") (pintype "passive"))
    )
    (net (code "44") (name "/INS.Grn") (class "Default")
      (node (ref "D3") (pin "4") (pinfunction "4_4") (pintype "passive"))
      (node (ref "R32") (pin "1") (pinfunction "1_1") (pintype "passive"))
    )
    (net (code "45") (name "/INS.Red") (class "Default")
      (node (ref "D3") (pin "2") (pinfunction "2_2") (pintype "passive"))
      (node (ref "R36") (pin "1") (pinfunction "1_1") (pintype "passive"))
    )
    (net (code "46") (name "/INV-UART-EN") (class "Default")
      (node (ref "U2") (pin "2") (pinfunction "1B_2") (pintype "input"))
      (node (ref "U2") (pin "5") (pinfunction "2A_5") (pintype "input"))
      (node (ref "U3") (pin "B1") (pinfunction "PE2_B1") (pintype "passive"))
    )
    (net (code "47") (name "/In-VSense") (class "Default")
      (node (ref "U3") (pin "E1") (pinfunction "PC31_E1") (pintype "passive"))
    )
    (net (code "48") (name "/LOG.blu") (class "Default")
      (node (ref "R10") (pin "2") (pinfunction "2_2") (pintype "passive"))
      (node (ref "U3") (pin "L10") (pinfunction "PA12_L10") (pintype "passive"))
    )
    (net (code "49") (name "/LOG.grn") (class "Default")
      (node (ref "R42") (pin "2") (pinfunction "2_2") (pintype "passive"))
      (node (ref "U3") (pin "M7") (pinfunction "PD23_M7") (pintype "passive"))
    )
    (net (code "50") (name "/LOG.red") (class "Default")
      (node (ref "R40") (pin "2") (pinfunction "2_2") (pintype "passive"))
      (node (ref "U3") (pin "J9") (pinfunction "PA11_J9") (pintype "passive"))
    )
    (net (code "51") (name "/Lblu") (class "Default")
      (node (ref "D2") (pin "3") (pinfunction "3_3") (pintype "passive"))
      (node (ref "R10") (pin "1") (pinfunction "1_1") (pintype "passive"))
    )
    (net (code "52") (name "/Lgrn") (class "Default")
      (node (ref "D2") (pin "4") (pinfunction "4_4") (pintype "passive"))
      (node (ref "R42") (pin "1") (pinfunction "1_1") (pintype "passive"))
    )
    (net (code "53") (name "/Lred") (class "Default")
      (node (ref "D2") (pin "2") (pinfunction "2_2") (pintype "passive"))
      (node (ref "R40") (pin "1") (pinfunction "1_1") (pintype "passive"))
    )
    (net (code "54") (name "/M-CHIP_ERASE") (class "Default")
      (node (ref "R53") (pin "2") (pinfunction "2_2") (pintype "passive"))
      (node (ref "U3") (pin "G12") (pinfunction "PB12_G12") (pintype "passive"))
    )
    (net (code "55") (name "/M-G1{slash}TXD1{slash}TIOA1") (class "Default")
      (node (ref "U2") (pin "1") (pinfunction "1A_1") (pintype "input"))
      (node (ref "U3") (pin "A12") (pinfunction "PB4_A12") (pintype "passive"))
      (node (ref "U3") (pin "L5") (pinfunction "PA15_L5") (pintype "passive"))
    )
    (net (code "56") (name "/M-G1{slash}TXD1{slash}TIOA1_INV") (class "Default")
      (node (ref "H8") (pin "5") (pinfunction "5_5") (pintype "passive"))
      (node (ref "U2") (pin "7") (pinfunction "1Y_7") (pintype "output"))
    )
    (net (code "57") (name "/M-G2{slash}RXD1{slash}TIOB1") (class "Default")
      (node (ref "U2") (pin "3") (pinfunction "2Y_3") (pintype "output"))
      (node (ref "U3") (pin "K2") (pinfunction "PA21_K2") (pintype "passive"))
      (node (ref "U3") (pin "K5") (pinfunction "PA16_K5") (pintype "passive"))
    )
    (net (code "58") (name "/M-G2{slash}RXD1{slash}TIOB1_INV") (class "Default")
      (node (ref "H8") (pin "6") (pinfunction "6_6") (pintype "passive"))
      (node (ref "U2") (pin "6") (pinfunction "2B_6") (pintype "input"))
    )
    (net (code "59") (name "/M-G3{slash}SCK1{slash}TIOA0{slash}QDA") (class "Default")
      (node (ref "H8") (pin "7") (pinfunction "7_7") (pintype "passive"))
      (node (ref "U3") (pin "C11") (pinfunction "PA0_C11") (pintype "passive"))
      (node (ref "U3") (pin "L4") (pinfunction "PA23_L4") (pintype "passive"))
    )
    (net (code "60") (name "/M-G4{slash}CS1{slash}TIOB0{slash}QDB") (class "Default")
      (node (ref "H8") (pin "8") (pinfunction "8_8") (pintype "passive"))
      (node (ref "U3") (pin "D12") (pinfunction "PA1_D12") (pintype "passive"))
      (node (ref "U3") (pin "L7") (pinfunction "PA24_L7") (pintype "passive"))
    )
    (net (code "61") (name "/M-G5{slash}DA0{slash}TIOA6{slash}AD4") (class "Default")
      (node (ref "H8") (pin "9") (pinfunction "9_9") (pintype "passive"))
      (node (ref "U3") (pin "B2") (pinfunction "PB13_B2") (pintype "passive"))
      (node (ref "U3") (pin "F3") (pinfunction "PC29_F3") (pintype "passive"))
      (node (ref "U3") (pin "L8") (pinfunction "PC5_L8") (pintype "passive"))
    )
    (net (code "62") (name "/M-G6{slash}DA1{slash}TIOB6{slash}AD5") (class "Default")
      (node (ref "H8") (pin "10") (pinfunction "10_10") (pintype "passive"))
      (node (ref "U3") (pin "D4") (pinfunction "PD0_D4") (pintype "passive"))
      (node (ref "U3") (pin "K7") (pinfunction "PC6_K7") (pintype "passive"))
    )
    (net (code "63") (name "/M-G7{slash}TIOB7{slash}AD10") (class "Default")
      (node (ref "H8") (pin "11") (pinfunction "11_11") (pintype "passive"))
      (node (ref "U3") (pin "E3") (pinfunction "PE3_E3") (pintype "passive"))
      (node (ref "U3") (pin "G11") (pinfunction "PC9_G11") (pintype "passive"))
    )
    (net (code "64") (name "/M-G8{slash}TIOB10{slash}AD4") (class "Default")
      (node (ref "H8") (pin "12") (pinfunction "12_12") (pintype "passive"))
      (node (ref "U3") (pin "J6") (pinfunction "PD27_J6") (pintype "passive"))
      (node (ref "U3") (pin "K1") (pinfunction "PE4_K1") (pintype "passive"))
    )
    (net (code "65") (name "/M-G9{slash}TIOA9{slash}AD1") (class "Default")
      (node (ref "H8") (pin "13") (pinfunction "13_13") (pintype "passive"))
      (node (ref "U3") (pin "C2") (pinfunction "PE0_C2") (pintype "passive"))
      (node (ref "U3") (pin "G2") (pinfunction "PC13_G2") (pintype "passive"))
    )
    (net (code "66") (name "/M-G10{slash}TIOB9{slash}AD2") (class "Default")
      (node (ref "H8") (pin "14") (pinfunction "14_14") (pintype "passive"))
      (node (ref "U3") (pin "A1") (pinfunction "PE1_A1") (pintype "passive"))
      (node (ref "U3") (pin "G1") (pinfunction "PC15_G1") (pintype "passive"))
    )
    (net (code "67") (name "/M-SW-CFG") (class "Default")
      (node (ref "S2") (pin "1") (pinfunction "1_1") (pintype "passive"))
      (node (ref "U3") (pin "L3") (pinfunction "PC3_L3") (pintype "passive"))
    )
    (net (code "68") (name "/M-SW-LOG") (class "Default")
      (node (ref "S3") (pin "1") (pinfunction "1_1") (pintype "passive"))
      (node (ref "U3") (pin "M4") (pinfunction "PC7_M4") (pintype "passive"))
    )
    (net (code "69") (name "/M-SWD.SWDCLK") (class "Default")
      (node (ref "H5") (pin "4") (pinfunction "4_4") (pintype "passive"))
      (node (ref "U3") (pin "F9") (pinfunction "PB7_F9") (pintype "passive"))
    )
    (net (code "70") (name "/M-SWD.SWDIO") (class "Default")
      (node (ref "H5") (pin "2") (pinfunction "2_2") (pintype "passive"))
      (node (ref "U3") (pin "J11") (pinfunction "PB6_J11") (pintype "passive"))
    )
    (net (code "71") (name "/M-SWD.SWO") (class "Default")
      (node (ref "H5") (pin "6") (pinfunction "6_6") (pintype "passive"))
      (node (ref "U3") (pin "C10") (pinfunction "PB5_C10") (pintype "passive"))
    )
    (net (code "72") (name "/M-USB.D_N") (class "Default")
      (node (ref "U3") (pin "B4") (pinfunction "HSDM_B4") (pintype "passive"))
    )
    (net (code "73") (name "/M-USB.D_P") (class "Default")
      (node (ref "U3") (pin "A4") (pinfunction "HSDP_A4") (pintype "passive"))
    )
    (net (code "74") (name "/M-USB.ID") (class "Default")
      (node (ref "U3") (pin "J1") (pinfunction "PA17_J1") (pintype "passive"))
    )
    (net (code "76") (name "/M-~{RESET}") (class "Default")
      (node (ref "C34") (pin "1") (pinfunction "1_1") (pintype "passive"))
      (node (ref "D7") (pin "C") (pinfunction "C_C") (pintype "passive"))
      (node (ref "H5") (pin "10") (pinfunction "10_10") (pintype "passive"))
      (node (ref "R9") (pin "1") (pinfunction "1_1") (pintype "passive"))
      (node (ref "S1") (pin "2") (pinfunction "2_2") (pintype "passive"))
      (node (ref "U3") (pin "H12") (pinfunction "RESET_H12") (pintype "passive"))
    )
    (net (code "77") (name "/RS232.RxD") (class "Default")
      (node (ref "U3") (pin "K10") (pinfunction "PD28_K10") (pintype "passive"))
    )
    (net (code "78") (name "/RS232.TxD") (class "Default")
      (node (ref "U3") (pin "M1") (pinfunction "PD30_M1") (pintype "passive"))
    )
    (net (code "80") (name "/SD.CLK") (class "Default")
      (node (ref "U3") (pin "K8") (pinfunction "PA25_K8") (pintype "passive"))
    )
    (net (code "81") (name "/SD.CMD") (class "Default")
      (node (ref "U3") (pin "C9") (pinfunction "PA28_C9") (pintype "passive"))
    )
    (net (code "82") (name "/SD.D0") (class "Default")
      (node (ref "U3") (pin "A10") (pinfunction "PA30_A10") (pintype "passive"))
    )
    (net (code "83") (name "/SD.D1") (class "Default")
      (node (ref "U3") (pin "C8") (pinfunction "PA31_C8") (pintype "passive"))
    )
    (net (code "84") (name "/SD.D2") (class "Default")
      (node (ref "U3") (pin "J8") (pinfunction "PA26_J8") (pintype "passive"))
    )
    (net (code "85") (name "/SD.D3") (class "Default")
      (node (ref "U3") (pin "J10") (pinfunction "PA27_J10") (pintype "passive"))
    )
    (net (code "86") (name "/SD.DETECT") (class "Default")
      (node (ref "U3") (pin "D11") (pinfunction "PC16_D11") (pintype "passive"))
    )
    (net (code "88") (name "/SP330-DUPLEX") (class "Default")
      (node (ref "U3") (pin "B10") (pinfunction "PC18_B10") (pintype "passive"))
    )
    (net (code "89") (name "/SP330-SHDN") (class "Default")
      (node (ref "U3") (pin "H1") (pinfunction "PA19_H1") (pintype "passive"))
    )
    (net (code "90") (name "/SP330-SLEW") (class "Default")
      (node (ref "U3") (pin "H2") (pinfunction "PA18_H2") (pintype "passive"))
    )
    (net (code "91") (name "/VBG") (class "Default")
      (node (ref "C4") (pin "1") (pinfunction "1_1") (pintype "passive"))
      (node (ref "R4") (pin "1") (pinfunction "1_1") (pintype "passive"))
      (node (ref "U3") (pin "C4") (pinfunction "VBG_C4") (pintype "passive"))
    )
    (net (code "92") (name "/VDDPLL") (class "Default")
      (node (ref "C44") (pin "1") (pinfunction "1_1") (pintype "passive"))
      (node (ref "I6") (pin "1") (pinfunction "1_1") (pintype "passive"))
      (node (ref "U3") (pin "J7") (pinfunction "VDDPLL_J7") (pintype "passive"))
    )
    (net (code "93") (name "/VDDPLLUSB") (class "Default")
      (node (ref "C35") (pin "1") (pinfunction "1_1") (pintype "passive"))
      (node (ref "I5") (pin "1") (pinfunction "1_1") (pintype "passive"))
      (node (ref "U3") (pin "F8") (pinfunction "VDDPLLUSB_F8") (pintype "passive"))
    )
    (net (code "94") (name "/VDDUTMIC") (class "Default")
      (node (ref "C49") (pin "1") (pinfunction "1_1") (pintype "passive"))
      (node (ref "I7") (pin "1") (pinfunction "1_1") (pintype "passive"))
      (node (ref "U3") (pin "B3") (pinfunction "VDDUTMIC_B3") (pintype "passive"))
    )
    (net (code "95") (name "/VREFP") (class "Default")
      (node (ref "C8") (pin "1") (pinfunction "1_1") (pintype "passive"))
      (node (ref "I2") (pin "1") (pinfunction "1_1") (pintype "passive"))
      (node (ref "U3") (pin "D1") (pinfunction "VREFP_D1") (pintype "passive"))
    )
    (net (code "96") (name "/WINC-LED.Rx") (class "Default")
      (node (ref "R28") (pin "2") (pinfunction "2_2") (pintype "passive"))
      (node (ref "U3") (pin "B12") (pinfunction "PC17_B12") (pintype "passive"))
    )
    (net (code "97") (name "/WINC-LED.Tx") (class "Default")
      (node (ref "R29") (pin "2") (pinfunction "2_2") (pintype "passive"))
      (node (ref "U3") (pin "C12") (pinfunction "PD10_C12") (pintype "passive"))
    )
    (net (code "98") (name "/WINC.Grn") (class "Default")
      (node (ref "D5") (pin "4") (pinfunction "4_4") (pintype "passive"))
      (node (ref "R28") (pin "1") (pinfunction "1_1") (pintype "passive"))
    )
    (net (code "99") (name "/WINC.Red") (class "Default")
      (node (ref "D5") (pin "2") (pinfunction "2_2") (pintype "passive"))
      (node (ref "R29") (pin "1") (pinfunction "1_1") (pintype "passive"))
    )
    (net (code "100") (name "/WiFi-EN") (class "Default")
      (node (ref "U3") (pin "C7") (pinfunction "PC22_C7") (pintype "passive"))
    )
    (net (code "101") (name "/WiFi-IRQN") (class "Default")
      (node (ref "U3") (pin "C6") (pinfunction "PC23_C6") (pintype "passive"))
    )
    (net (code "102") (name "/WiFi-RST") (class "Default")
      (node (ref "U3") (pin "A7") (pinfunction "PC21_A7") (pintype "passive"))
    )
    (net (code "103") (name "/WiFi-SPI.CS") (class "Default")
      (node (ref "U3") (pin "C5") (pinfunction "PC25_C5") (pintype "passive"))
    )
    (net (code "104") (name "/WiFi-SPI.MISO") (class "Default")
      (node (ref "U3") (pin "F2") (pinfunction "PC26_F2") (pintype "passive"))
    )
    (net (code "105") (name "/WiFi-SPI.MOSI") (class "Default")
      (node (ref "U3") (pin "E2") (pinfunction "PC27_E2") (pintype "passive"))
    )
    (net (code "106") (name "/WiFi-SPI.SCLK") (class "Default")
      (node (ref "U3") (pin "B6") (pinfunction "PC24_B6") (pintype "passive"))
    )
    (net (code "108") (name "/XBee-DTR") (class "Default")
      (node (ref "U3") (pin "B5") (pinfunction "PD1_B5") (pintype "passive"))
    )
    (net (code "109") (name "/XBee-RST") (class "Default")
      (node (ref "U3") (pin "A6") (pinfunction "PA29_A6") (pintype "passive"))
    )
    (net (code "110") (name "/XBee-Ser.CTS") (class "Default")
      (node (ref "U3") (pin "J3") (pinfunction "PB3_J3") (pintype "passive"))
    )
    (net (code "111") (name "/XBee-Ser.RTS") (class "Default")
      (node (ref "U3") (pin "J2") (pinfunction "PB2_J2") (pintype "passive"))
    )
    (net (code "112") (name "/XBee-Ser.RxD") (class "Default")
      (node (ref "U3") (pin "G3") (pinfunction "PB1_G3") (pintype "passive"))
    )
    (net (code "113") (name "/XBee-Ser.TxD") (class "Default")
      (node (ref "U3") (pin "H4") (pinfunction "PB0_H4") (pintype "passive"))
    )
    (net (code "115") (name "/XBee-Supply-En") (class "Default")
      (node (ref "U3") (pin "L11") (pinfunction "PD17_L11") (pintype "passive"))
    )
    (net (code "116") (name "/Xin") (class "Default")
      (node (ref "U3") (pin "A2") (pinfunction "PB9_A2") (pintype "passive"))
      (node (ref "Y2") (pin "3") (pinfunction "OUT_3") (pintype "output"))
    )
    (net (code "117") (name "/Xin32") (class "Default")
      (node (ref "C7") (pin "1") (pinfunction "1_1") (pintype "passive"))
      (node (ref "U3") (pin "L2") (pinfunction "PA7_L2") (pintype "passive"))
      (node (ref "Y1") (pin "2") (pinfunction "2_2") (pintype "passive"))
    )
    (net (code "118") (name "/Xout") (class "Default")
      (node (ref "U3") (pin "A3") (pinfunction "PB8_A3") (pintype "passive"))
    )
    (net (code "119") (name "/Xout32") (class "Default")
      (node (ref "C6") (pin "1") (pinfunction "1_1") (pintype "passive"))
      (node (ref "U3") (pin "M2") (pinfunction "PA8_M2") (pintype "passive"))
      (node (ref "Y1") (pin "1") (pinfunction "1_1") (pintype "passive"))
    )
    (net (code "120") (name "/uINS-Data-Rdy") (class "Default")
      (node (ref "U3") (pin "A5") (pinfunction "PD2_A5") (pintype "passive"))
    )
    (net (code "121") (name "/uINS-SPI-EN") (class "Default")
      (node (ref "U3") (pin "A9") (pinfunction "PC20_A9") (pintype "passive"))
    )
    (net (code "122") (name "/uINS-Ser0.RxD") (class "Default")
      (node (ref "U3") (pin "B9") (pinfunction "PA6_B9") (pintype "passive"))
    )
    (net (code "123") (name "/uINS-Ser0.TxD") (class "Default")
      (node (ref "U3") (pin "M11") (pinfunction "PA5_M11") (pintype "passive"))
    )
    (net (code "125") (name "/uINS-Ser1.CS") (class "Default")
      (node (ref "U3") (pin "G10") (pinfunction "PD12_G10") (pintype "passive"))
    )
    (net (code "126") (name "/uINS-Ser1.RxD{slash}MOSI") (class "Default")
      (node (ref "U3") (pin "H9") (pinfunction "PD21_H9") (pintype "passive"))
      (node (ref "U3") (pin "L9") (pinfunction "PA10_L9") (pintype "passive"))
    )
    (net (code "127") (name "/uINS-Ser1.SCLK") (class "Default")
      (node (ref "U3") (pin "M8") (pinfunction "PD22_M8") (pintype "passive"))
    )
    (net (code "128") (name "/uINS-Ser1.TxD{slash}MISO") (class "Default")
      (node (ref "U3") (pin "K9") (pinfunction "PD20_K9") (pintype "passive"))
      (node (ref "U3") (pin "M12") (pinfunction "PA9_M12") (pintype "passive"))
    )
    (net (code "130") (name "BEE.3V3") (class "Default")
      (node (ref "H4") (pin "4") (pinfunction "4_4") (pintype "passive"))
      (node (ref "H4") (pin "5") (pinfunction "5_5") (pintype "passive"))
      (node (ref "H4") (pin "6") (pinfunction "6_6") (pintype "passive"))
    )
    (net (code "131") (name "GND") (class "Default")
      (node (ref "C11") (pin "2") (pinfunction "2_2") (pintype "passive"))
      (node (ref "C13") (pin "1") (pinfunction "1_1") (pintype "passive"))
      (node (ref "C19") (pin "2") (pinfunction "2_2") (pintype "passive"))
      (node (ref "C26") (pin "1") (pinfunction "1_1") (pintype "passive"))
      (node (ref "C30") (pin "1") (pinfunction "1_1") (pintype "passive"))
      (node (ref "C34") (pin "2") (pinfunction "2_2") (pintype "passive"))
      (node (ref "C35") (pin "2") (pinfunction "2_2") (pintype "passive"))
      (node (ref "C36") (pin "2") (pinfunction "2_2") (pintype "passive"))
      (node (ref "C37") (pin "2") (pinfunction "2_2") (pintype "passive"))
      (node (ref "C38") (pin "2") (pinfunction "2_2") (pintype "passive"))
      (node (ref "C39") (pin "2") (pinfunction "2_2") (pintype "passive"))
      (node (ref "C4") (pin "2") (pinfunction "2_2") (pintype "passive"))
      (node (ref "C40") (pin "2") (pinfunction "2_2") (pintype "passive"))
      (node (ref "C42") (pin "2") (pinfunction "2_2") (pintype "passive"))
      (node (ref "C43") (pin "2") (pinfunction "2_2") (pintype "passive"))
      (node (ref "C44") (pin "2") (pinfunction "2_2") (pintype "passive"))
      (node (ref "C45") (pin "2") (pinfunction "2_2") (pintype "passive"))
      (node (ref "C46") (pin "2") (pinfunction "2_2") (pintype "passive"))
      (node (ref "C47") (pin "2") (pinfunction "2_2") (pintype "passive"))
      (node (ref "C48") (pin "2") (pinfunction "2_2") (pintype "passive"))
      (node (ref "C49") (pin "2") (pinfunction "2_2") (pintype "passive"))
      (node (ref "C5") (pin "1") (pinfunction "1_1") (pintype "passive"))
      (node (ref "C50") (pin "2") (pinfunction "2_2") (pintype "passive"))
      (node (ref "C53") (pin "2") (pinfunction "2_2") (pintype "passive"))
      (node (ref "C6") (pin "2") (pinfunction "2_2") (pintype "passive"))
      (node (ref "C7") (pin "2") (pinfunction "2_2") (pintype "passive"))
      (node (ref "C8") (pin "2") (pinfunction "2_2") (pintype "passive"))
      (node (ref "C9") (pin "1") (pinfunction "1_1") (pintype "passive"))
      (node (ref "H4") (pin "0") (pinfunction "0_0") (pintype "passive"))
      (node (ref "H4") (pin "1") (pinfunction "1_1") (pintype "passive"))
      (node (ref "H4") (pin "2") (pinfunction "2_2") (pintype "passive"))
      (node (ref "H4") (pin "3") (pinfunction "3_3") (pintype "passive"))
      (node (ref "H5") (pin "3") (pinfunction "3_3") (pintype "passive"))
      (node (ref "H5") (pin "5") (pinfunction "5_5") (pintype "passive"))
      (node (ref "H5") (pin "9") (pinfunction "9_9") (pintype "passive"))
      (node (ref "H8") (pin "0") (pinfunction "0_0") (pintype "passive"))
      (node (ref "H8") (pin "1") (pinfunction "1_1") (pintype "passive"))
      (node (ref "H8") (pin "2") (pinfunction "2_2") (pintype "passive"))
      (node (ref "R4") (pin "2") (pinfunction "2_2") (pintype "passive"))
      (node (ref "S1") (pin "1") (pinfunction "1_1") (pintype "passive"))
      (node (ref "S2") (pin "2") (pinfunction "2_2") (pintype "passive"))
      (node (ref "S3") (pin "2") (pinfunction "2_2") (pintype "passive"))
      (node (ref "U2") (pin "4") (pinfunction "GND_4") (pintype "power_in"))
      (node (ref "U3") (pin "D2") (pinfunction "VREFN_D2") (pintype "passive"))
      (node (ref "U3") (pin "D5") (pinfunction "GNDANA_D5") (pintype "passive"))
      (node (ref "U3") (pin "E5") (pinfunction "GNDUTMI_E5") (pintype "passive"))
      (node (ref "U3") (pin "E6") (pinfunction "GNDPLLUSB_E6") (pintype "passive"))
      (node (ref "U3") (pin "F5") (pinfunction "GND_F5") (pintype "power_in"))
      (node (ref "U3") (pin "F6") (pinfunction "GND_F6") (pintype "power_in"))
      (node (ref "U3") (pin "F7") (pinfunction "GNDPLL_F7") (pintype "passive"))
      (node (ref "U3") (pin "G4") (pinfunction "GND_G4") (pintype "power_in"))
      (node (ref "U3") (pin "G5") (pinfunction "GND_G5") (pintype "power_in"))
      (node (ref "U3") (pin "G6") (pinfunction "GND_G6") (pintype "power_in"))
      (node (ref "U3") (pin "G7") (pinfunction "GND_G7") (pintype "power_in"))
      (node (ref "U3") (pin "J4") (pinfunction "PC1_J4") (pintype "passive"))
      (node (ref "Y2") (pin "2") (pinfunction "GND_2") (pintype "passive"))
    )
    (net (code "132") (name "Net-(D7-PadA)") (class "Default")
      (node (ref "D7") (pin "A") (pinfunction "A_A") (pintype "passive"))
      (node (ref "R54") (pin "2") (pinfunction "2_2") (pintype "passive"))
    )
    (net (code "133") (name "VDDOUT") (class "Default")
      (node (ref "C36") (pin "1") (pinfunction "1_1") (pintype "passive"))
      (node (ref "C37") (pin "1") (pinfunction "1_1") (pintype "passive"))
      (node (ref "C38") (pin "1") (pinfunction "1_1") (pintype "passive"))
      (node (ref "C40") (pin "1") (pinfunction "1_1") (pintype "passive"))
      (node (ref "C47") (pin "1") (pinfunction "1_1") (pintype "passive"))
      (node (ref "C48") (pin "1") (pinfunction "1_1") (pintype "passive"))
      (node (ref "C50") (pin "1") (pinfunction "1_1") (pintype "passive"))
      (node (ref "I6") (pin "2") (pinfunction "2_2") (pintype "passive"))
      (node (ref "I7") (pin "2") (pinfunction "2_2") (pintype "passive"))
      (node (ref "U3") (pin "C3") (pinfunction "VDDOUT_C3") (pintype "passive"))
      (node (ref "U3") (pin "E8") (pinfunction "VDDCORE_E8") (pintype "passive"))
      (node (ref "U3") (pin "H5") (pinfunction "VDDCORE_H5") (pintype "passive"))
      (node (ref "U3") (pin "H8") (pinfunction "VDDCORE_H8") (pintype "passive"))
    )
    (net (code "134") (name "unconnected-(D3-Pad3)") (class "Default")
      (node (ref "D3") (pin "3") (pinfunction "3_3") (pintype "passive"))
    )
    (net (code "135") (name "unconnected-(D4-Pad3)") (class "Default")
      (node (ref "D4") (pin "3") (pinfunction "3_3") (pintype "passive"))
    )
    (net (code "136") (name "unconnected-(D5-Pad3)") (class "Default")
      (node (ref "D5") (pin "3") (pinfunction "3_3") (pintype "passive"))
    )
    (net (code "137") (name "unconnected-(H5-Pad7)") (class "Default")
      (node (ref "H5") (pin "7") (pinfunction "7_7") (pintype "passive"))
    )
    (net (code "138") (name "unconnected-(H5-Pad8)") (class "Default")
      (node (ref "H5") (pin "8") (pinfunction "8_8") (pintype "passive"))
    )
    (net (code "139") (name "unconnected-(U3-JTAGSEL-PadB11)") (class "Default")
      (node (ref "U3") (pin "B11") (pinfunction "JTAGSEL_B11") (pintype "passive"))
    )
    (net (code "140") (name "unconnected-(U3-PA14-PadK6)") (class "Default")
      (node (ref "U3") (pin "K6") (pinfunction "PA14_K6") (pintype "passive"))
    )
    (net (code "141") (name "unconnected-(U3-PA22-PadK3)") (class "Default")
      (node (ref "U3") (pin "K3") (pinfunction "PA22_K3") (pintype "passive"))
    )
    (net (code "142") (name "unconnected-(U3-PC4-PadJ5)") (class "Default")
      (node (ref "U3") (pin "J5") (pinfunction "PC4_J5") (pintype "passive"))
    )
    (net (code "143") (name "unconnected-(U3-PC19-PadD8)") (class "Default")
      (node (ref "U3") (pin "D8") (pinfunction "PC19_D8") (pintype "passive"))
    )
    (net (code "144") (name "unconnected-(U3-PD5-PadD7)") (class "Default")
      (node (ref "U3") (pin "D7") (pinfunction "PD5_D7") (pintype "passive"))
    )
    (net (code "145") (name "unconnected-(U3-PD8-PadE9)") (class "Default")
      (node (ref "U3") (pin "E9") (pinfunction "PD8_E9") (pintype "passive"))
    )
    (net (code "146") (name "unconnected-(U3-PD9-PadD9)") (class "Default")
      (node (ref "U3") (pin "D9") (pinfunction "PD9_D9") (pintype "passive"))
    )
    (net (code "147") (name "unconnected-(U3-PD11-PadE11)") (class "Default")
      (node (ref "U3") (pin "E11") (pinfunction "PD11_E11") (pintype "passive"))
    )
    (net (code "148") (name "unconnected-(U3-PD13-PadG9)") (class "Default")
      (node (ref "U3") (pin "G9") (pinfunction "PD13_G9") (pintype "passive"))
    )
    (net (code "149") (name "unconnected-(U3-PD14-PadH10)") (class "Default")
      (node (ref "U3") (pin "H10") (pinfunction "PD14_H10") (pintype "passive"))
    )
    (net (code "150") (name "unconnected-(U3-PD24-PadM6)") (class "Default")
      (node (ref "U3") (pin "M6") (pinfunction "PD24_M6") (pintype "passive"))
    )
    (net (code "151") (name "unconnected-(U3-PD29-PadD10)") (class "Default")
      (node (ref "U3") (pin "D10") (pinfunction "PD29_D10") (pintype "passive"))
    )
    (net (code "152") (name "unconnected-(U3-PD31-PadD3)") (class "Default")
      (node (ref "U3") (pin "D3") (pinfunction "PD31_D3") (pintype "passive"))
    )
    (net (code "153") (name "unconnected-(U3-PE5-PadL1)") (class "Default")
      (node (ref "U3") (pin "L1") (pinfunction "PE5_L1") (pintype "passive"))
    )
    (net (code "154") (name "unconnected-(U3-TST-PadH11)") (class "Default")
      (node (ref "U3") (pin "H11") (pinfunction "TST_H11") (pintype "passive"))
    )
  )
)
